# BeetleMeterV1.net
KiCad netlist of a schematic drawn in Altium Designer
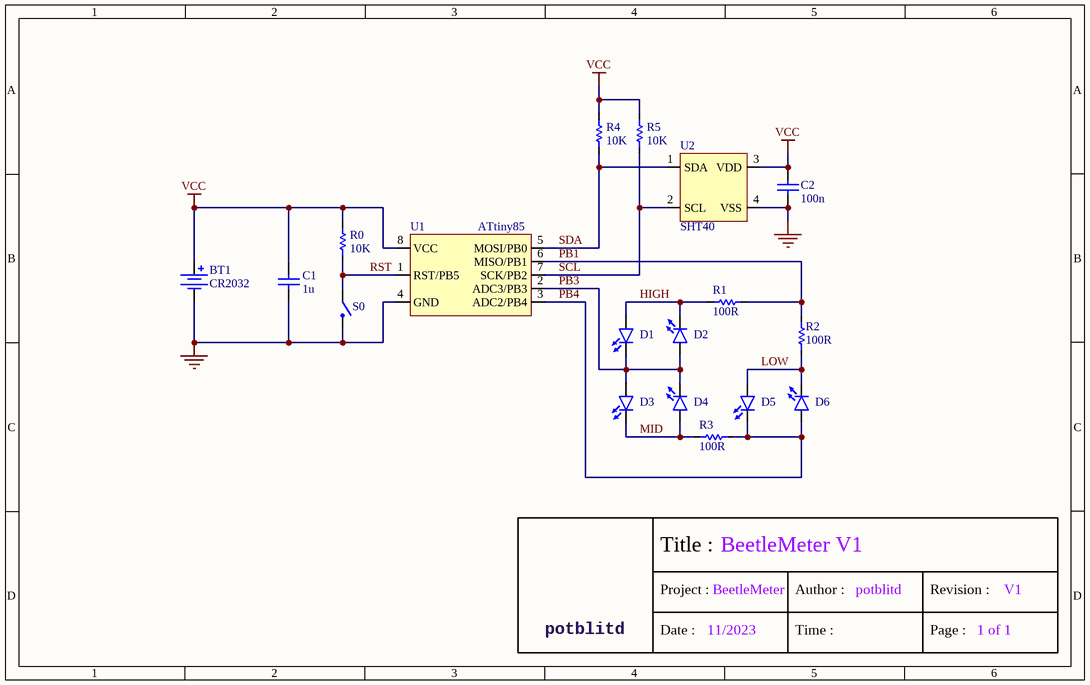
[diagram p0: BeetleMeterV1.SchDoc]

(export (version "E")
  (design (tool "Eeschema 10.0.6"))
  (components
    (comp (ref "BT1")
      (value "CR2032")
      (footprint "CR2032-TH")
      (description "Coin cell battery 3V")
      (libsource (lib "AltiumLib") (part "Battery 3V"))
    )
    (comp (ref "C1")
      (value "Capacitor")
      (footprint "0603C")
      (description "Capacitor 1uF")
      (fields (field (name "ALTIUM_VALUE") "1u"))
      (libsource (lib "Simulation Generic Components") (part "Capacitor"))
    )
    (comp (ref "C2")
      (value "100n")
      (footprint "0603C")
      (description "Capacitor 100nF ±10% 50V")
      (fields (field (name "Comment") "Capacitor"))
      (libsource (lib "Simulation Generic Components") (part "Capacitor"))
    )
    (comp (ref "D1")
      (value "R")
      (footprint "0805D")
      (description "General LED symbol")
      (libsource (lib "AltiumLib") (part "LED"))
    )
    (comp (ref "D2")
      (value "R")
      (footprint "0805D")
      (description "General LED symbol")
      (libsource (lib "AltiumLib") (part "LED"))
    )
    (comp (ref "D3")
      (value "R")
      (footprint "0805D")
      (description "General LED symbol")
      (libsource (lib "AltiumLib") (part "LED"))
    )
    (comp (ref "D4")
      (value "R")
      (footprint "0805D")
      (description "General LED symbol")
      (libsource (lib "AltiumLib") (part "LED"))
    )
    (comp (ref "D5")
      (value "R")
      (footprint "0805D")
      (description "General LED symbol")
      (libsource (lib "AltiumLib") (part "LED"))
    )
    (comp (ref "D6")
      (value "R")
      (footprint "0805D")
      (description "General LED symbol")
      (libsource (lib "AltiumLib") (part "LED"))
    )
    (comp (ref "R0")
      (value "10K")
      (footprint "0603R")
      (description "Resistor 10kΩ ±1% 1/16W")
      (fields (field (name "Comment") "Resistor"))
      (libsource (lib "Simulation Generic Components") (part "RES"))
    )
    (comp (ref "R1")
      (value "100R")
      (footprint "0603R")
      (description "Resistor 100Ω")
      (fields (field (name "Comment") "Resistor"))
      (libsource (lib "AltiumLib") (part "RES"))
    )
    (comp (ref "R2")
      (value "100R")
      (footprint "0603R")
      (description "Resistor 100Ω")
      (fields (field (name "Comment") "Resistor"))
      (libsource (lib "AltiumLib") (part "RES"))
    )
    (comp (ref "R3")
      (value "100R")
      (footprint "0603R")
      (description "Resistor 100Ω")
      (fields (field (name "Comment") "Resistor"))
      (libsource (lib "AltiumLib") (part "RES"))
    )
    (comp (ref "R4")
      (value "10K")
      (footprint "0603R")
      (description "Resistor 10kΩ ±1% 1/16W")
      (fields (field (name "Comment") "Resistor"))
      (libsource (lib "Simulation Generic Components") (part "RES"))
    )
    (comp (ref "R5")
      (value "10K")
      (footprint "0603R")
      (description "Resistor 10kΩ ±1% 1/16W")
      (fields (field (name "Comment") "Resistor"))
      (libsource (lib "Simulation Generic Components") (part "RES"))
    )
    (comp (ref "S0")
      (value "~")
      (footprint "SW_6*6")
      (description "2-positions switch open-closed")
      (libsource (lib "AltiumLib") (part "Switch-2"))
    )
    (comp (ref "U1")
      (value "ATtiny85")
      (footprint "DIP-8 - SMD")
      (description "tiny AVR 8-pin microcontroller")
      (libsource (lib "AltiumLib") (part "ATtiny13A-5"))
    )
    (comp (ref "U2")
      (value "SHT40")
      (footprint "DFN-4-EP(1.5x1.5)")
      (description "SHT40 temperature and humidity sensor")
      (libsource (lib "AltiumLib") (part "SHT40"))
    )
  )
  (nets
    (net (code "1") (name "/HIGH") (class "Default")
      (node (ref "D1") (pin "1") (pintype "passive"))
      (node (ref "D2") (pin "2") (pintype "passive"))
      (node (ref "R1") (pin "1") (pinfunction "1_1") (pintype "passive"))
    )
    (net (code "2") (name "/LOW") (class "Default")
      (node (ref "D5") (pin "1") (pintype "passive"))
      (node (ref "D6") (pin "2") (pintype "passive"))
      (node (ref "R2") (pin "1") (pinfunction "1_1") (pintype "passive"))
    )
    (net (code "3") (name "/MID") (class "Default")
      (node (ref "D3") (pin "2") (pintype "passive"))
      (node (ref "D4") (pin "1") (pintype "passive"))
      (node (ref "R3") (pin "2") (pinfunction "2_2") (pintype "passive"))
    )
    (net (code "4") (name "/PB1") (class "Default")
      (node (ref "R1") (pin "2") (pinfunction "2_2") (pintype "passive"))
      (node (ref "R2") (pin "2") (pinfunction "2_2") (pintype "passive"))
      (node (ref "U1") (pin "6") (pinfunction "MISO/PB1_6") (pintype "passive"))
    )
    (net (code "5") (name "/PB3") (class "Default")
      (node (ref "D1") (pin "2") (pintype "passive"))
      (node (ref "D2") (pin "1") (pintype "passive"))
      (node (ref "D3") (pin "1") (pintype "passive"))
      (node (ref "D4") (pin "2") (pintype "passive"))
      (node (ref "U1") (pin "2") (pinfunction "ADC3/PB3_2") (pintype "passive"))
    )
    (net (code "6") (name "/PB4") (class "Default")
      (node (ref "D5") (pin "2") (pintype "passive"))
      (node (ref "D6") (pin "1") (pintype "passive"))
      (node (ref "R3") (pin "1") (pinfunction "1_1") (pintype "passive"))
      (node (ref "U1") (pin "3") (pinfunction "ADC2/PB4_3") (pintype "passive"))
    )
    (net (code "7") (name "/RST") (class "Default")
      (node (ref "R0") (pin "1") (pinfunction "1_1") (pintype "passive"))
      (node (ref "S0") (pin "1") (pinfunction "1_1") (pintype "passive"))
      (node (ref "U1") (pin "1") (pinfunction "RST/PB5_1") (pintype "passive"))
    )
    (net (code "8") (name "/SCL") (class "Default")
      (node (ref "R5") (pin "1") (pinfunction "1_1") (pintype "passive"))
      (node (ref "U1") (pin "7") (pinfunction "SCK/PB2_7") (pintype "passive"))
      (node (ref "U2") (pin "2") (pinfunction "SCL_2") (pintype "passive"))
    )
    (net (code "9") (name "/SDA") (class "Default")
      (node (ref "R4") (pin "1") (pinfunction "1_1") (pintype "passive"))
      (node (ref "U1") (pin "5") (pinfunction "MOSI/PB0_5") (pintype "passive"))
      (node (ref "U2") (pin "1") (pinfunction "SDA_1") (pintype "passive"))
    )
    (net (code "10") (name "GND") (class "Default")
      (node (ref "BT1") (pin "2") (pinfunction "-_2") (pintype "passive"))
      (node (ref "C1") (pin "1") (pinfunction "1_1") (pintype "passive"))
      (node (ref "C2") (pin "2") (pinfunction "2_2") (pintype "passive"))
      (node (ref "S0") (pin "2") (pinfunction "2_2") (pintype "passive"))
      (node (ref "U1") (pin "4") (pinfunction "GND_4") (pintype "passive"))
      (node (ref "U2") (pin "4") (pinfunction "VSS_4") (pintype "passive"))
    )
    (net (code "11") (name "VCC") (class "Default")
      (node (ref "BT1") (pin "1") (pinfunction "+_1") (pintype "passive"))
      (node (ref "C1") (pin "2") (pinfunction "2_2") (pintype "passive"))
      (node (ref "C2") (pin "1") (pinfunction "1_1") (pintype "passive"))
      (node (ref "R0") (pin "2") (pinfunction "2_2") (pintype "passive"))
      (node (ref "R4") (pin "2") (pinfunction "2_2") (pintype "passive"))
      (node (ref "R5") (pin "2") (pinfunction "2_2") (pintype "passive"))
      (node (ref "U1") (pin "8") (pinfunction "VCC_8") (pintype "passive"))
      (node (ref "U2") (pin "3") (pinfunction "VDD_3") (pintype "passive"))
    )
  )
)
